# TC364_MainBoard_Core_V1_1.net
KiCad netlist of a schematic drawn in Altium Designer
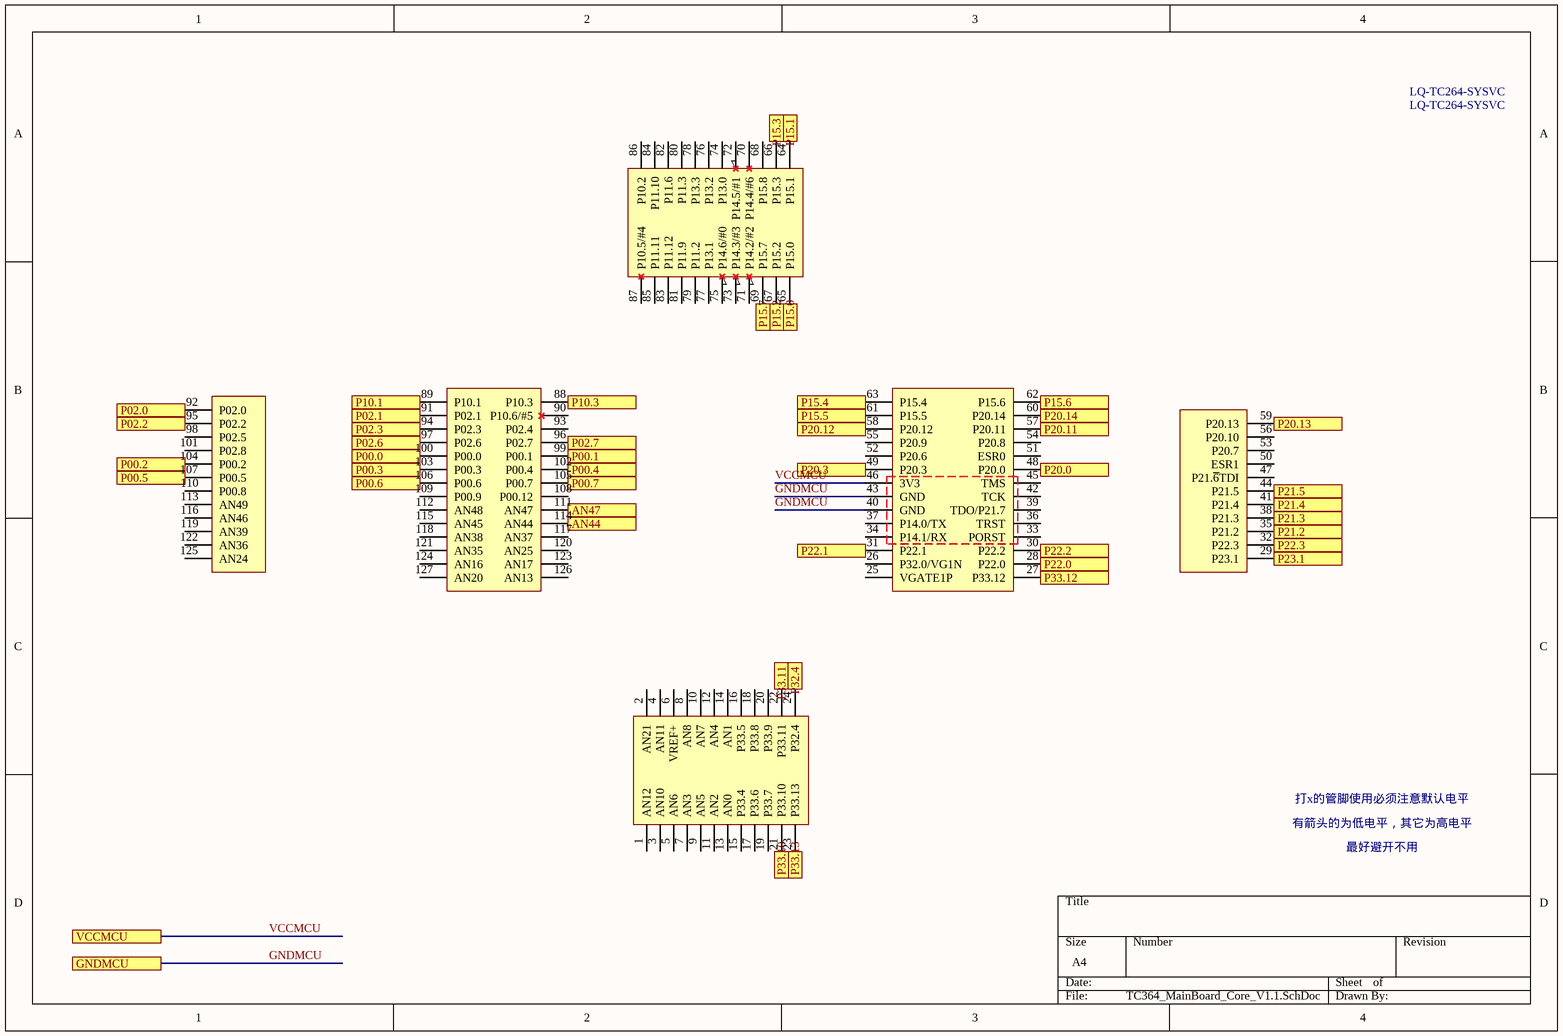
[diagram p0: TC364_MainBoard_Core_V1.1.SchDoc]

(export (version "E")
  (design (tool "Eeschema 10.0.6"))
  (components
    (comp (ref "LQ-TC264-SYSVC")
      (value "LQ-TC264-SYSVC")
      (footprint "LQ-TC264-SYSVC-S")
      (libsource (lib "LQ-TC264-SYSVC封装") (part "LQ-TC264-SYSVC"))
    )
  )
  (nets
    (net (code "1") (name "/AN44") (class "Default")
      (node (ref "LQ-TC264-SYSVC") (pin "114") (pinfunction "AN44_114") (pintype "passive"))
    )
    (net (code "2") (name "/AN47") (class "Default")
      (node (ref "LQ-TC264-SYSVC") (pin "111") (pinfunction "AN47_111") (pintype "passive"))
    )
    (net (code "3") (name "/GNDMCU") (class "Default")
      (node (ref "LQ-TC264-SYSVC") (pin "40") (pinfunction "GND_40") (pintype "passive"))
      (node (ref "LQ-TC264-SYSVC") (pin "43") (pinfunction "GND_43") (pintype "passive"))
    )
    (net (code "4") (name "/P00.0") (class "Default")
      (node (ref "LQ-TC264-SYSVC") (pin "100") (pinfunction "P00.0_100") (pintype "passive"))
    )
    (net (code "5") (name "/P00.1") (class "Default")
      (node (ref "LQ-TC264-SYSVC") (pin "99") (pinfunction "P00.1_99") (pintype "passive"))
    )
    (net (code "6") (name "/P00.2") (class "Default")
      (node (ref "LQ-TC264-SYSVC") (pin "104") (pinfunction "P00.2_104") (pintype "passive"))
    )
    (net (code "7") (name "/P00.3") (class "Default")
      (node (ref "LQ-TC264-SYSVC") (pin "103") (pinfunction "P00.3_103") (pintype "passive"))
    )
    (net (code "8") (name "/P00.4") (class "Default")
      (node (ref "LQ-TC264-SYSVC") (pin "102") (pinfunction "P00.4_102") (pintype "passive"))
    )
    (net (code "9") (name "/P00.5") (class "Default")
      (node (ref "LQ-TC264-SYSVC") (pin "107") (pinfunction "P00.5_107") (pintype "passive"))
    )
    (net (code "10") (name "/P00.6") (class "Default")
      (node (ref "LQ-TC264-SYSVC") (pin "106") (pinfunction "P00.6_106") (pintype "passive"))
    )
    (net (code "11") (name "/P00.7") (class "Default")
      (node (ref "LQ-TC264-SYSVC") (pin "105") (pinfunction "P00.7_105") (pintype "passive"))
    )
    (net (code "12") (name "/P02.0") (class "Default")
      (node (ref "LQ-TC264-SYSVC") (pin "92") (pinfunction "P02.0_92") (pintype "passive"))
    )
    (net (code "13") (name "/P02.1") (class "Default")
      (node (ref "LQ-TC264-SYSVC") (pin "91") (pinfunction "P02.1_91") (pintype "passive"))
    )
    (net (code "14") (name "/P02.2") (class "Default")
      (node (ref "LQ-TC264-SYSVC") (pin "95") (pinfunction "P02.2_95") (pintype "passive"))
    )
    (net (code "15") (name "/P02.3") (class "Default")
      (node (ref "LQ-TC264-SYSVC") (pin "94") (pinfunction "P02.3_94") (pintype "passive"))
    )
    (net (code "16") (name "/P02.6") (class "Default")
      (node (ref "LQ-TC264-SYSVC") (pin "97") (pinfunction "P02.6_97") (pintype "passive"))
    )
    (net (code "17") (name "/P02.7") (class "Default")
      (node (ref "LQ-TC264-SYSVC") (pin "96") (pinfunction "P02.7_96") (pintype "passive"))
    )
    (net (code "18") (name "/P10.1") (class "Default")
      (node (ref "LQ-TC264-SYSVC") (pin "89") (pinfunction "P10.1_89") (pintype "passive"))
    )
    (net (code "19") (name "/P10.3") (class "Default")
      (node (ref "LQ-TC264-SYSVC") (pin "88") (pinfunction "P10.3_88") (pintype "passive"))
    )
    (net (code "20") (name "/P15.0") (class "Default")
      (node (ref "LQ-TC264-SYSVC") (pin "65") (pinfunction "P15.0_65") (pintype "passive"))
    )
    (net (code "21") (name "/P15.1") (class "Default")
      (node (ref "LQ-TC264-SYSVC") (pin "64") (pinfunction "P15.1_64") (pintype "passive"))
    )
    (net (code "22") (name "/P15.2") (class "Default")
      (node (ref "LQ-TC264-SYSVC") (pin "67") (pinfunction "P15.2_67") (pintype "passive"))
    )
    (net (code "23") (name "/P15.3") (class "Default")
      (node (ref "LQ-TC264-SYSVC") (pin "66") (pinfunction "P15.3_66") (pintype "passive"))
    )
    (net (code "24") (name "/P15.4") (class "Default")
      (node (ref "LQ-TC264-SYSVC") (pin "63") (pinfunction "P15.4_63") (pintype "passive"))
    )
    (net (code "25") (name "/P15.5") (class "Default")
      (node (ref "LQ-TC264-SYSVC") (pin "61") (pinfunction "P15.5_61") (pintype "passive"))
    )
    (net (code "26") (name "/P15.6") (class "Default")
      (node (ref "LQ-TC264-SYSVC") (pin "62") (pinfunction "P15.6_62") (pintype "passive"))
    )
    (net (code "27") (name "/P15.7") (class "Default")
      (node (ref "LQ-TC264-SYSVC") (pin "69") (pinfunction "P15.7_69") (pintype "passive"))
    )
    (net (code "28") (name "/P20.0") (class "Default")
      (node (ref "LQ-TC264-SYSVC") (pin "48") (pinfunction "P20.0_48") (pintype "passive"))
    )
    (net (code "29") (name "/P20.3") (class "Default")
      (node (ref "LQ-TC264-SYSVC") (pin "49") (pinfunction "P20.3_49") (pintype "passive"))
    )
    (net (code "30") (name "/P20.11") (class "Default")
      (node (ref "LQ-TC264-SYSVC") (pin "57") (pinfunction "P20.11_57") (pintype "passive"))
    )
    (net (code "31") (name "/P20.12") (class "Default")
      (node (ref "LQ-TC264-SYSVC") (pin "58") (pinfunction "P20.12_58") (pintype "passive"))
    )
    (net (code "32") (name "/P20.13") (class "Default")
      (node (ref "LQ-TC264-SYSVC") (pin "59") (pinfunction "P20.13_59") (pintype "passive"))
    )
    (net (code "33") (name "/P20.14") (class "Default")
      (node (ref "LQ-TC264-SYSVC") (pin "60") (pinfunction "P20.14_60") (pintype "passive"))
    )
    (net (code "34") (name "/P21.2") (class "Default")
      (node (ref "LQ-TC264-SYSVC") (pin "35") (pinfunction "P21.2_35") (pintype "passive"))
    )
    (net (code "35") (name "/P21.3") (class "Default")
      (node (ref "LQ-TC264-SYSVC") (pin "38") (pinfunction "P21.3_38") (pintype "passive"))
    )
    (net (code "36") (name "/P21.4") (class "Default")
      (node (ref "LQ-TC264-SYSVC") (pin "41") (pinfunction "P21.4_41") (pintype "passive"))
    )
    (net (code "37") (name "/P21.5") (class "Default")
      (node (ref "LQ-TC264-SYSVC") (pin "44") (pinfunction "P21.5_44") (pintype "passive"))
    )
    (net (code "38") (name "/P22.0") (class "Default")
      (node (ref "LQ-TC264-SYSVC") (pin "28") (pinfunction "P22.0_28") (pintype "passive"))
    )
    (net (code "39") (name "/P22.1") (class "Default")
      (node (ref "LQ-TC264-SYSVC") (pin "31") (pinfunction "P22.1_31") (pintype "passive"))
    )
    (net (code "40") (name "/P22.2") (class "Default")
      (node (ref "LQ-TC264-SYSVC") (pin "30") (pinfunction "P22.2_30") (pintype "passive"))
    )
    (net (code "41") (name "/P22.3") (class "Default")
      (node (ref "LQ-TC264-SYSVC") (pin "32") (pinfunction "P22.3_32") (pintype "passive"))
    )
    (net (code "42") (name "/P23.1") (class "Default")
      (node (ref "LQ-TC264-SYSVC") (pin "29") (pinfunction "P23.1_29") (pintype "passive"))
    )
    (net (code "43") (name "/P32.4") (class "Default")
      (node (ref "LQ-TC264-SYSVC") (pin "24") (pinfunction "P32.4_24") (pintype "passive"))
    )
    (net (code "44") (name "/P33.10") (class "Default")
      (node (ref "LQ-TC264-SYSVC") (pin "21") (pinfunction "P33.10_21") (pintype "passive"))
    )
    (net (code "45") (name "/P33.11") (class "Default")
      (node (ref "LQ-TC264-SYSVC") (pin "22") (pinfunction "P33.11_22") (pintype "passive"))
    )
    (net (code "46") (name "/P33.12") (class "Default")
      (node (ref "LQ-TC264-SYSVC") (pin "27") (pinfunction "P33.12_27") (pintype "passive"))
    )
    (net (code "47") (name "/P33.13") (class "Default")
      (node (ref "LQ-TC264-SYSVC") (pin "23") (pinfunction "P33.13_23") (pintype "passive"))
    )
    (net (code "48") (name "/VCCMCU") (class "Default")
      (node (ref "LQ-TC264-SYSVC") (pin "46") (pinfunction "3V3_46") (pintype "passive"))
    )
    (net (code "49") (name "unconnected-(LQ-TC264-SYSVC-AN0-Pad13)") (class "Default")
      (node (ref "LQ-TC264-SYSVC") (pin "13") (pinfunction "AN0_13") (pintype "passive"))
    )
    (net (code "50") (name "unconnected-(LQ-TC264-SYSVC-AN1-Pad14)") (class "Default")
      (node (ref "LQ-TC264-SYSVC") (pin "14") (pinfunction "AN1_14") (pintype "passive"))
    )
    (net (code "51") (name "unconnected-(LQ-TC264-SYSVC-AN2-Pad11)") (class "Default")
      (node (ref "LQ-TC264-SYSVC") (pin "11") (pinfunction "AN2_11") (pintype "passive"))
    )
    (net (code "52") (name "unconnected-(LQ-TC264-SYSVC-AN3-Pad7)") (class "Default")
      (node (ref "LQ-TC264-SYSVC") (pin "7") (pinfunction "AN3_7") (pintype "passive"))
    )
    (net (code "53") (name "unconnected-(LQ-TC264-SYSVC-AN4-Pad12)") (class "Default")
      (node (ref "LQ-TC264-SYSVC") (pin "12") (pinfunction "AN4_12") (pintype "passive"))
    )
    (net (code "54") (name "unconnected-(LQ-TC264-SYSVC-AN5-Pad9)") (class "Default")
      (node (ref "LQ-TC264-SYSVC") (pin "9") (pinfunction "AN5_9") (pintype "passive"))
    )
    (net (code "55") (name "unconnected-(LQ-TC264-SYSVC-AN6-Pad5)") (class "Default")
      (node (ref "LQ-TC264-SYSVC") (pin "5") (pinfunction "AN6_5") (pintype "passive"))
    )
    (net (code "56") (name "unconnected-(LQ-TC264-SYSVC-AN7-Pad10)") (class "Default")
      (node (ref "LQ-TC264-SYSVC") (pin "10") (pinfunction "AN7_10") (pintype "passive"))
    )
    (net (code "57") (name "unconnected-(LQ-TC264-SYSVC-AN8-Pad8)") (class "Default")
      (node (ref "LQ-TC264-SYSVC") (pin "8") (pinfunction "AN8_8") (pintype "passive"))
    )
    (net (code "58") (name "unconnected-(LQ-TC264-SYSVC-AN10-Pad3)") (class "Default")
      (node (ref "LQ-TC264-SYSVC") (pin "3") (pinfunction "AN10_3") (pintype "passive"))
    )
    (net (code "59") (name "unconnected-(LQ-TC264-SYSVC-AN11-Pad4)") (class "Default")
      (node (ref "LQ-TC264-SYSVC") (pin "4") (pinfunction "AN11_4") (pintype "passive"))
    )
    (net (code "60") (name "unconnected-(LQ-TC264-SYSVC-AN12-Pad1)") (class "Default")
      (node (ref "LQ-TC264-SYSVC") (pin "1") (pinfunction "AN12_1") (pintype "passive"))
    )
    (net (code "61") (name "unconnected-(LQ-TC264-SYSVC-AN13-Pad126)") (class "Default")
      (node (ref "LQ-TC264-SYSVC") (pin "126") (pinfunction "AN13_126") (pintype "passive"))
    )
    (net (code "62") (name "unconnected-(LQ-TC264-SYSVC-AN16-Pad124)") (class "Default")
      (node (ref "LQ-TC264-SYSVC") (pin "124") (pinfunction "AN16_124") (pintype "passive"))
    )
    (net (code "63") (name "unconnected-(LQ-TC264-SYSVC-AN17-Pad123)") (class "Default")
      (node (ref "LQ-TC264-SYSVC") (pin "123") (pinfunction "AN17_123") (pintype "passive"))
    )
    (net (code "64") (name "unconnected-(LQ-TC264-SYSVC-AN20-Pad127)") (class "Default")
      (node (ref "LQ-TC264-SYSVC") (pin "127") (pinfunction "AN20_127") (pintype "passive"))
    )
    (net (code "65") (name "unconnected-(LQ-TC264-SYSVC-AN21-Pad2)") (class "Default")
      (node (ref "LQ-TC264-SYSVC") (pin "2") (pinfunction "AN21_2") (pintype "passive"))
    )
    (net (code "66") (name "unconnected-(LQ-TC264-SYSVC-AN24-Pad125)") (class "Default")
      (node (ref "LQ-TC264-SYSVC") (pin "125") (pinfunction "AN24_125") (pintype "passive"))
    )
    (net (code "67") (name "unconnected-(LQ-TC264-SYSVC-AN25-Pad120)") (class "Default")
      (node (ref "LQ-TC264-SYSVC") (pin "120") (pinfunction "AN25_120") (pintype "passive"))
    )
    (net (code "68") (name "unconnected-(LQ-TC264-SYSVC-AN35-Pad121)") (class "Default")
      (node (ref "LQ-TC264-SYSVC") (pin "121") (pinfunction "AN35_121") (pintype "passive"))
    )
    (net (code "69") (name "unconnected-(LQ-TC264-SYSVC-AN36-Pad122)") (class "Default")
      (node (ref "LQ-TC264-SYSVC") (pin "122") (pinfunction "AN36_122") (pintype "passive"))
    )
    (net (code "70") (name "unconnected-(LQ-TC264-SYSVC-AN37-Pad117)") (class "Default")
      (node (ref "LQ-TC264-SYSVC") (pin "117") (pinfunction "AN37_117") (pintype "passive"))
    )
    (net (code "71") (name "unconnected-(LQ-TC264-SYSVC-AN38-Pad118)") (class "Default")
      (node (ref "LQ-TC264-SYSVC") (pin "118") (pinfunction "AN38_118") (pintype "passive"))
    )
    (net (code "72") (name "unconnected-(LQ-TC264-SYSVC-AN39-Pad119)") (class "Default")
      (node (ref "LQ-TC264-SYSVC") (pin "119") (pinfunction "AN39_119") (pintype "passive"))
    )
    (net (code "73") (name "unconnected-(LQ-TC264-SYSVC-AN45-Pad115)") (class "Default")
      (node (ref "LQ-TC264-SYSVC") (pin "115") (pinfunction "AN45_115") (pintype "passive"))
    )
    (net (code "74") (name "unconnected-(LQ-TC264-SYSVC-AN46-Pad116)") (class "Default")
      (node (ref "LQ-TC264-SYSVC") (pin "116") (pinfunction "AN46_116") (pintype "passive"))
    )
    (net (code "75") (name "unconnected-(LQ-TC264-SYSVC-AN48-Pad112)") (class "Default")
      (node (ref "LQ-TC264-SYSVC") (pin "112") (pinfunction "AN48_112") (pintype "passive"))
    )
    (net (code "76") (name "unconnected-(LQ-TC264-SYSVC-AN49-Pad113)") (class "Default")
      (node (ref "LQ-TC264-SYSVC") (pin "113") (pinfunction "AN49_113") (pintype "passive"))
    )
    (net (code "77") (name "unconnected-(LQ-TC264-SYSVC-ESR0-Pad51)") (class "Default")
      (node (ref "LQ-TC264-SYSVC") (pin "51") (pinfunction "ESR0_51") (pintype "passive"))
    )
    (net (code "78") (name "unconnected-(LQ-TC264-SYSVC-ESR1-Pad50)") (class "Default")
      (node (ref "LQ-TC264-SYSVC") (pin "50") (pinfunction "ESR1_50") (pintype "passive"))
    )
    (net (code "79") (name "unconnected-(LQ-TC264-SYSVC-P00.8-Pad110)") (class "Default")
      (node (ref "LQ-TC264-SYSVC") (pin "110") (pinfunction "P00.8_110") (pintype "passive"))
    )
    (net (code "80") (name "unconnected-(LQ-TC264-SYSVC-P00.9-Pad109)") (class "Default")
      (node (ref "LQ-TC264-SYSVC") (pin "109") (pinfunction "P00.9_109") (pintype "passive"))
    )
    (net (code "81") (name "unconnected-(LQ-TC264-SYSVC-P00.12-Pad108)") (class "Default")
      (node (ref "LQ-TC264-SYSVC") (pin "108") (pinfunction "P00.12_108") (pintype "passive"))
    )
    (net (code "82") (name "unconnected-(LQ-TC264-SYSVC-P02.4-Pad93)") (class "Default")
      (node (ref "LQ-TC264-SYSVC") (pin "93") (pinfunction "P02.4_93") (pintype "passive"))
    )
    (net (code "83") (name "unconnected-(LQ-TC264-SYSVC-P02.5-Pad98)") (class "Default")
      (node (ref "LQ-TC264-SYSVC") (pin "98") (pinfunction "P02.5_98") (pintype "passive"))
    )
    (net (code "84") (name "unconnected-(LQ-TC264-SYSVC-P02.8-Pad101)") (class "Default")
      (node (ref "LQ-TC264-SYSVC") (pin "101") (pinfunction "P02.8_101") (pintype "passive"))
    )
    (net (code "85") (name "unconnected-(LQ-TC264-SYSVC-P10.2-Pad86)") (class "Default")
      (node (ref "LQ-TC264-SYSVC") (pin "86") (pinfunction "P10.2_86") (pintype "passive"))
    )
    (net (code "86") (name "unconnected-(LQ-TC264-SYSVC-P10.5{slash}#4-Pad87)") (class "Default")
      (node (ref "LQ-TC264-SYSVC") (pin "87") (pinfunction "P10.5/#4_87") (pintype "passive"))
    )
    (net (code "87") (name "unconnected-(LQ-TC264-SYSVC-P10.6{slash}#5-Pad90)") (class "Default")
      (node (ref "LQ-TC264-SYSVC") (pin "90") (pinfunction "P10.6/#5_90") (pintype "passive"))
    )
    (net (code "88") (name "unconnected-(LQ-TC264-SYSVC-P11.2-Pad79)") (class "Default")
      (node (ref "LQ-TC264-SYSVC") (pin "79") (pinfunction "P11.2_79") (pintype "passive"))
    )
    (net (code "89") (name "unconnected-(LQ-TC264-SYSVC-P11.3-Pad80)") (class "Default")
      (node (ref "LQ-TC264-SYSVC") (pin "80") (pinfunction "P11.3_80") (pintype "passive"))
    )
    (net (code "90") (name "unconnected-(LQ-TC264-SYSVC-P11.6-Pad82)") (class "Default")
      (node (ref "LQ-TC264-SYSVC") (pin "82") (pinfunction "P11.6_82") (pintype "passive"))
    )
    (net (code "91") (name "unconnected-(LQ-TC264-SYSVC-P11.9-Pad81)") (class "Default")
      (node (ref "LQ-TC264-SYSVC") (pin "81") (pinfunction "P11.9_81") (pintype "passive"))
    )
    (net (code "92") (name "unconnected-(LQ-TC264-SYSVC-P11.10-Pad84)") (class "Default")
      (node (ref "LQ-TC264-SYSVC") (pin "84") (pinfunction "P11.10_84") (pintype "passive"))
    )
    (net (code "93") (name "unconnected-(LQ-TC264-SYSVC-P11.11-Pad85)") (class "Default")
      (node (ref "LQ-TC264-SYSVC") (pin "85") (pinfunction "P11.11_85") (pintype "passive"))
    )
    (net (code "94") (name "unconnected-(LQ-TC264-SYSVC-P11.12-Pad83)") (class "Default")
      (node (ref "LQ-TC264-SYSVC") (pin "83") (pinfunction "P11.12_83") (pintype "passive"))
    )
    (net (code "95") (name "unconnected-(LQ-TC264-SYSVC-P13.0-Pad74)") (class "Default")
      (node (ref "LQ-TC264-SYSVC") (pin "74") (pinfunction "P13.0_74") (pintype "passive"))
    )
    (net (code "96") (name "unconnected-(LQ-TC264-SYSVC-P13.1-Pad77)") (class "Default")
      (node (ref "LQ-TC264-SYSVC") (pin "77") (pinfunction "P13.1_77") (pintype "passive"))
    )
    (net (code "97") (name "unconnected-(LQ-TC264-SYSVC-P13.2-Pad76)") (class "Default")
      (node (ref "LQ-TC264-SYSVC") (pin "76") (pinfunction "P13.2_76") (pintype "passive"))
    )
    (net (code "98") (name "unconnected-(LQ-TC264-SYSVC-P13.3-Pad78)") (class "Default")
      (node (ref "LQ-TC264-SYSVC") (pin "78") (pinfunction "P13.3_78") (pintype "passive"))
    )
    (net (code "99") (name "unconnected-(LQ-TC264-SYSVC-P14.0{slash}TX-Pad37)") (class "Default")
      (node (ref "LQ-TC264-SYSVC") (pin "37") (pinfunction "P14.0/TX_37") (pintype "passive"))
    )
    (net (code "100") (name "unconnected-(LQ-TC264-SYSVC-P14.1{slash}RX-Pad34)") (class "Default")
      (node (ref "LQ-TC264-SYSVC") (pin "34") (pinfunction "P14.1/RX_34") (pintype "passive"))
    )
    (net (code "101") (name "unconnected-(LQ-TC264-SYSVC-P14.2{slash}#2-Pad71)") (class "Default")
      (node (ref "LQ-TC264-SYSVC") (pin "71") (pinfunction "P14.2/#2_71") (pintype "passive"))
    )
    (net (code "102") (name "unconnected-(LQ-TC264-SYSVC-P14.3{slash}#3-Pad73)") (class "Default")
      (node (ref "LQ-TC264-SYSVC") (pin "73") (pinfunction "P14.3/#3_73") (pintype "passive"))
    )
    (net (code "103") (name "unconnected-(LQ-TC264-SYSVC-P14.4{slash}#6-Pad70)") (class "Default")
      (node (ref "LQ-TC264-SYSVC") (pin "70") (pinfunction "P14.4/#6_70") (pintype "passive"))
    )
    (net (code "104") (name "unconnected-(LQ-TC264-SYSVC-P14.5{slash}#1-Pad72)") (class "Default")
      (node (ref "LQ-TC264-SYSVC") (pin "72") (pinfunction "P14.5/#1_72") (pintype "passive"))
    )
    (net (code "105") (name "unconnected-(LQ-TC264-SYSVC-P14.6{slash}#0-Pad75)") (class "Default")
      (node (ref "LQ-TC264-SYSVC") (pin "75") (pinfunction "P14.6/#0_75") (pintype "passive"))
    )
    (net (code "106") (name "unconnected-(LQ-TC264-SYSVC-P15.8-Pad68)") (class "Default")
      (node (ref "LQ-TC264-SYSVC") (pin "68") (pinfunction "P15.8_68") (pintype "passive"))
    )
    (net (code "107") (name "unconnected-(LQ-TC264-SYSVC-P20.6-Pad52)") (class "Default")
      (node (ref "LQ-TC264-SYSVC") (pin "52") (pinfunction "P20.6_52") (pintype "passive"))
    )
    (net (code "108") (name "unconnected-(LQ-TC264-SYSVC-P20.7-Pad53)") (class "Default")
      (node (ref "LQ-TC264-SYSVC") (pin "53") (pinfunction "P20.7_53") (pintype "passive"))
    )
    (net (code "109") (name "unconnected-(LQ-TC264-SYSVC-P20.8-Pad54)") (class "Default")
      (node (ref "LQ-TC264-SYSVC") (pin "54") (pinfunction "P20.8_54") (pintype "passive"))
    )
    (net (code "110") (name "unconnected-(LQ-TC264-SYSVC-P20.9-Pad55)") (class "Default")
      (node (ref "LQ-TC264-SYSVC") (pin "55") (pinfunction "P20.9_55") (pintype "passive"))
    )
    (net (code "111") (name "unconnected-(LQ-TC264-SYSVC-P20.10-Pad56)") (class "Default")
      (node (ref "LQ-TC264-SYSVC") (pin "56") (pinfunction "P20.10_56") (pintype "passive"))
    )
    (net (code "112") (name "unconnected-(LQ-TC264-SYSVC-P21.~{6}TDI-Pad47)") (class "Default")
      (node (ref "LQ-TC264-SYSVC") (pin "47") (pinfunction "P21.~{6}TDI_47") (pintype "passive"))
    )
    (net (code "113") (name "unconnected-(LQ-TC264-SYSVC-P32.0{slash}VG1N-Pad26)") (class "Default")
      (node (ref "LQ-TC264-SYSVC") (pin "26") (pinfunction "P32.0/VG1N_26") (pintype "passive"))
    )
    (net (code "114") (name "unconnected-(LQ-TC264-SYSVC-P33.4-Pad15)") (class "Default")
      (node (ref "LQ-TC264-SYSVC") (pin "15") (pinfunction "P33.4_15") (pintype "passive"))
    )
    (net (code "115") (name "unconnected-(LQ-TC264-SYSVC-P33.5-Pad16)") (class "Default")
      (node (ref "LQ-TC264-SYSVC") (pin "16") (pinfunction "P33.5_16") (pintype "passive"))
    )
    (net (code "116") (name "unconnected-(LQ-TC264-SYSVC-P33.6-Pad17)") (class "Default")
      (node (ref "LQ-TC264-SYSVC") (pin "17") (pinfunction "P33.6_17") (pintype "passive"))
    )
    (net (code "117") (name "unconnected-(LQ-TC264-SYSVC-P33.7-Pad19)") (class "Default")
      (node (ref "LQ-TC264-SYSVC") (pin "19") (pinfunction "P33.7_19") (pintype "passive"))
    )
    (net (code "118") (name "unconnected-(LQ-TC264-SYSVC-P33.8-Pad18)") (class "Default")
      (node (ref "LQ-TC264-SYSVC") (pin "18") (pinfunction "P33.8_18") (pintype "passive"))
    )
    (net (code "119") (name "unconnected-(LQ-TC264-SYSVC-P33.9-Pad20)") (class "Default")
      (node (ref "LQ-TC264-SYSVC") (pin "20") (pinfunction "P33.9_20") (pintype "passive"))
    )
    (net (code "120") (name "unconnected-(LQ-TC264-SYSVC-PORST-Pad33)") (class "Default")
      (node (ref "LQ-TC264-SYSVC") (pin "33") (pinfunction "PORST_33") (pintype "passive"))
    )
    (net (code "121") (name "unconnected-(LQ-TC264-SYSVC-TCK-Pad42)") (class "Default")
      (node (ref "LQ-TC264-SYSVC") (pin "42") (pinfunction "TCK_42") (pintype "passive"))
    )
    (net (code "122") (name "unconnected-(LQ-TC264-SYSVC-TDO{slash}P21.7-Pad39)") (class "Default")
      (node (ref "LQ-TC264-SYSVC") (pin "39") (pinfunction "TDO/P21.7_39") (pintype "passive"))
    )
    (net (code "123") (name "unconnected-(LQ-TC264-SYSVC-TMS-Pad45)") (class "Default")
      (node (ref "LQ-TC264-SYSVC") (pin "45") (pinfunction "TMS_45") (pintype "passive"))
    )
    (net (code "124") (name "unconnected-(LQ-TC264-SYSVC-TRST-Pad36)") (class "Default")
      (node (ref "LQ-TC264-SYSVC") (pin "36") (pinfunction "TRST_36") (pintype "passive"))
    )
    (net (code "125") (name "unconnected-(LQ-TC264-SYSVC-VGATE1P-Pad25)") (class "Default")
      (node (ref "LQ-TC264-SYSVC") (pin "25") (pinfunction "VGATE1P_25") (pintype "passive"))
    )
    (net (code "126") (name "unconnected-(LQ-TC264-SYSVC-VREF+-Pad6)") (class "Default")
      (node (ref "LQ-TC264-SYSVC") (pin "6") (pinfunction "VREF+_6") (pintype "passive"))
    )
  )
)
